# cv_switch.net
KiCad netlist of a schematic drawn in EAGLE
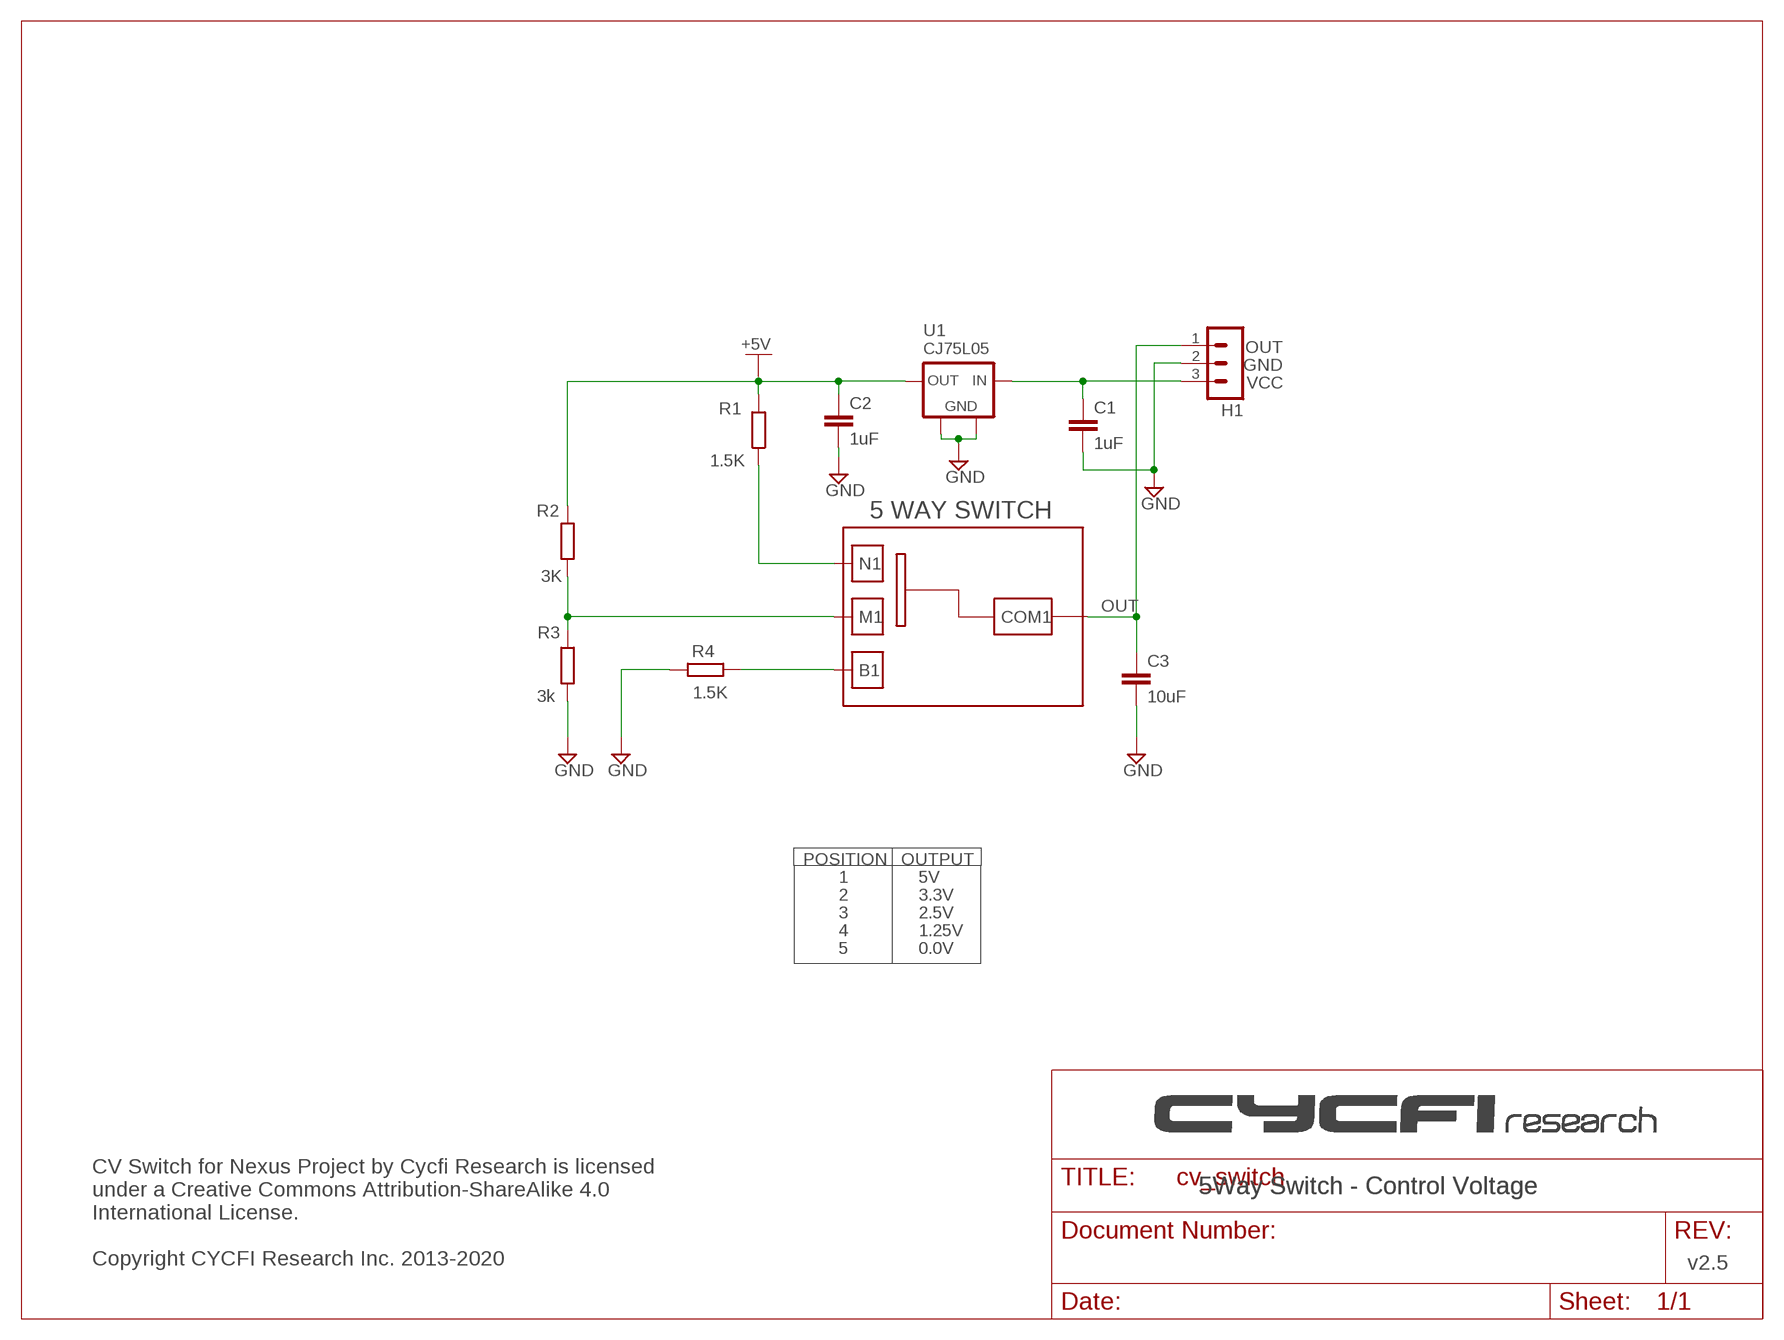
[diagram p0: schematic, sheet 1]

(export (version "E")
  (design (tool "Eeschema 10.0.6"))
  (components
    (comp (ref "C1")
      (value "1uF")
      (footprint "eagle-import:C0603")
      (libsource (lib "eagle-import") (part "C-EUC0603"))
    )
    (comp (ref "C2")
      (value "1uF")
      (footprint "eagle-import:C0603")
      (libsource (lib "eagle-import") (part "C-EUC0603"))
    )
    (comp (ref "C3")
      (value "10uF")
      (footprint "eagle-import:C0603")
      (libsource (lib "eagle-import") (part "C-EUC0603"))
    )
    (comp (ref "H1")
      (value "MA03-1_EDITED")
      (footprint "eagle-import:MA03-1_")
      (libsource (lib "eagle-import") (part "MA03-1_EDITED"))
    )
    (comp (ref "R1")
      (value "1.5K")
      (footprint "eagle-import:R0402")
      (libsource (lib "eagle-import") (part "R-EU_R0402"))
    )
    (comp (ref "R2")
      (value "3K")
      (footprint "eagle-import:R0402")
      (libsource (lib "eagle-import") (part "R-EU_R0402"))
    )
    (comp (ref "R3")
      (value "3k")
      (footprint "eagle-import:R0402")
      (libsource (lib "eagle-import") (part "R-EU_R0402"))
    )
    (comp (ref "R4")
      (value "1.5K")
      (footprint "eagle-import:R0402")
      (libsource (lib "eagle-import") (part "R-EU_R0402"))
    )
    (comp (ref "U$1")
      (value "5WAY_SW_1")
      (footprint "eagle-import:5WAY_SW_CASTELLATED")
      (libsource (lib "eagle-import") (part "5WAY_SW_1"))
    )
    (comp (ref "U1")
      (value "CJ75L05")
      (footprint "eagle-import:SOT89")
      (libsource (lib "eagle-import") (part "L78LXX"))
    )
  )
  (nets
    (net (code "1") (name "/+5V") (class "Default")
      (node (ref "C2") (pin "1") (pinfunction "1_1") (pintype "passive"))
      (node (ref "R1") (pin "2") (pinfunction "2_2") (pintype "passive"))
      (node (ref "R2") (pin "2") (pinfunction "2_2") (pintype "passive"))
      (node (ref "U1") (pin "1") (pinfunction "IN_1") (pintype "input"))
    )
    (net (code "2") (name "/OUT") (class "Default")
      (node (ref "C3") (pin "1") (pinfunction "1_1") (pintype "passive"))
      (node (ref "H1") (pin "1") (pinfunction "1_1") (pintype "passive"))
      (node (ref "U$1") (pin "COM1") (pinfunction "COM1_COM1") (pintype "bidirectional"))
    )
    (net (code "3") (name "GND") (class "Default")
      (node (ref "C1") (pin "2") (pinfunction "2_2") (pintype "passive"))
      (node (ref "C2") (pin "2") (pinfunction "2_2") (pintype "passive"))
      (node (ref "C3") (pin "2") (pinfunction "2_2") (pintype "passive"))
      (node (ref "H1") (pin "2") (pinfunction "2_2") (pintype "passive"))
      (node (ref "R3") (pin "1") (pinfunction "1_1") (pintype "passive"))
      (node (ref "R4") (pin "1") (pinfunction "1_1") (pintype "passive"))
      (node (ref "U1") (pin "2") (pinfunction "GND_2") (pintype "input"))
      (node (ref "U1") (pin "2@1") (pinfunction "GND1_2@1") (pintype "input"))
    )
    (net (code "4") (name "Net-(R1-Pad1)") (class "Default")
      (node (ref "R1") (pin "1") (pinfunction "1_1") (pintype "passive"))
      (node (ref "U$1") (pin "N1") (pinfunction "N1_N1") (pintype "bidirectional"))
    )
    (net (code "5") (name "Net-(R2-Pad1)") (class "Default")
      (node (ref "R2") (pin "1") (pinfunction "1_1") (pintype "passive"))
      (node (ref "R3") (pin "2") (pinfunction "2_2") (pintype "passive"))
      (node (ref "U$1") (pin "M1") (pinfunction "M1_M1") (pintype "bidirectional"))
    )
    (net (code "6") (name "Net-(R4-Pad2)") (class "Default")
      (node (ref "R4") (pin "2") (pinfunction "2_2") (pintype "passive"))
      (node (ref "U$1") (pin "B1") (pinfunction "B1_B1") (pintype "bidirectional"))
    )
    (net (code "7") (name "Net-(U1-OUT)") (class "Default")
      (node (ref "C1") (pin "1") (pinfunction "1_1") (pintype "passive"))
      (node (ref "H1") (pin "3") (pinfunction "3_3") (pintype "passive"))
      (node (ref "U1") (pin "3") (pinfunction "OUT_3") (pintype "passive"))
    )
  )
)
